# controller.net
KiCad netlist of a schematic drawn in EAGLE
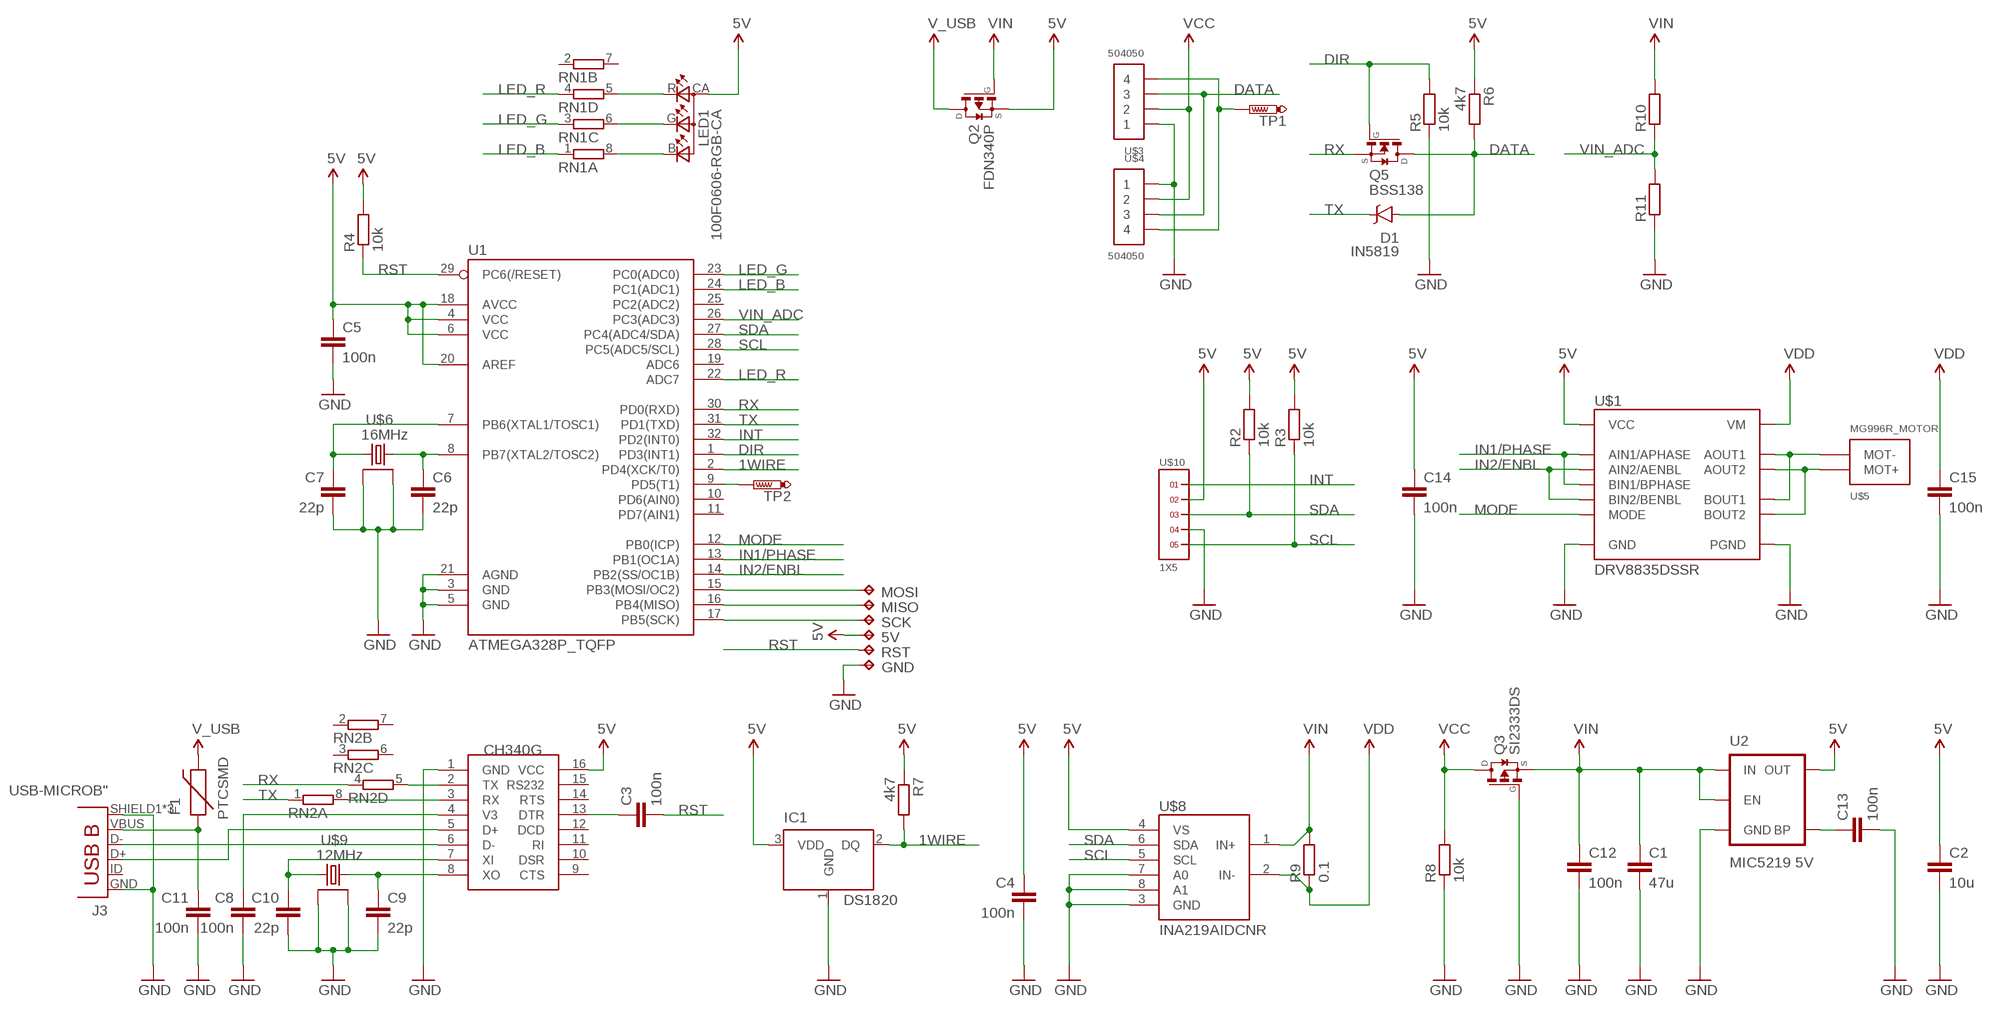
[diagram p0: schematic, sheet 1]

(export (version "E")
  (design (tool "Eeschema 10.0.6"))
  (components
    (comp (ref "5V")
      (value "TPTP07SQ")
      (footprint "eagle-import:TP07SQ")
      (libsource (lib "eagle-import") (part "TPTP07SQ"))
    )
    (comp (ref "C1")
      (value "47u")
      (footprint "eagle-import:C1206")
      (libsource (lib "eagle-import") (part "C-EUC1206"))
    )
    (comp (ref "C2")
      (value "10u")
      (footprint "eagle-import:C0603K")
      (libsource (lib "eagle-import") (part "C-EUC0603K"))
    )
    (comp (ref "C3")
      (value "100n")
      (footprint "eagle-import:C0402K")
      (libsource (lib "eagle-import") (part "C-EUC0402K"))
    )
    (comp (ref "C4")
      (value "100n")
      (footprint "eagle-import:C0402K")
      (libsource (lib "eagle-import") (part "C-EUC0402K"))
    )
    (comp (ref "C5")
      (value "100n")
      (footprint "eagle-import:C0402K")
      (libsource (lib "eagle-import") (part "C-EUC0402K"))
    )
    (comp (ref "C6")
      (value "22p")
      (footprint "eagle-import:C0402K")
      (libsource (lib "eagle-import") (part "C-EUC0402K"))
    )
    (comp (ref "C7")
      (value "22p")
      (footprint "eagle-import:C0402K")
      (libsource (lib "eagle-import") (part "C-EUC0402K"))
    )
    (comp (ref "C8")
      (value "100n")
      (footprint "eagle-import:C0402K")
      (libsource (lib "eagle-import") (part "C-EUC0402K"))
    )
    (comp (ref "C9")
      (value "22p")
      (footprint "eagle-import:C0402K")
      (libsource (lib "eagle-import") (part "C-EUC0402K"))
    )
    (comp (ref "C10")
      (value "22p")
      (footprint "eagle-import:C0402K")
      (libsource (lib "eagle-import") (part "C-EUC0402K"))
    )
    (comp (ref "C11")
      (value "100n")
      (footprint "eagle-import:C0402K")
      (libsource (lib "eagle-import") (part "C-EUC0402K"))
    )
    (comp (ref "C12")
      (value "100n")
      (footprint "eagle-import:C0402K")
      (libsource (lib "eagle-import") (part "C-EUC0402K"))
    )
    (comp (ref "C13")
      (value "100n")
      (footprint "eagle-import:C0402K")
      (libsource (lib "eagle-import") (part "C-EUC0402K"))
    )
    (comp (ref "C14")
      (value "100n")
      (footprint "eagle-import:C0402K")
      (libsource (lib "eagle-import") (part "C-EUC0402K"))
    )
    (comp (ref "C15")
      (value "100n")
      (footprint "eagle-import:C0402K")
      (libsource (lib "eagle-import") (part "C-EUC0402K"))
    )
    (comp (ref "D1")
      (value "IN5819")
      (footprint "eagle-import:SMA-DIODE")
      (libsource (lib "eagle-import") (part "MBRA140"))
    )
    (comp (ref "F1")
      (value "PTCSMD")
      (footprint "eagle-import:PTC-1206")
      (libsource (lib "eagle-import") (part "PTCSMD"))
    )
    (comp (ref "GND")
      (value "TPTP07SQ")
      (footprint "eagle-import:TP07SQ")
      (libsource (lib "eagle-import") (part "TPTP07SQ"))
    )
    (comp (ref "IC1")
      (value "DS1820")
      (footprint "eagle-import:TO-92")
      (libsource (lib "eagle-import") (part "DS1820"))
    )
    (comp (ref "J3")
      (value "USB-MICROB\"")
      (footprint "eagle-import:USB-B-MICRO-SMD_V03")
      (libsource (lib "eagle-import") (part "USB-MICROB{dblquote}"))
    )
    (comp (ref "LED1")
      (value "100F0606-RGB-CA")
      (footprint "eagle-import:1616")
      (libsource (lib "eagle-import") (part "100F0606-RGB-CA"))
    )
    (comp (ref "MISO")
      (value "TPTP07SQ")
      (footprint "eagle-import:TP07SQ")
      (libsource (lib "eagle-import") (part "TPTP07SQ"))
    )
    (comp (ref "MOSI")
      (value "TPTP07SQ")
      (footprint "eagle-import:TP07SQ")
      (libsource (lib "eagle-import") (part "TPTP07SQ"))
    )
    (comp (ref "Q2")
      (value "FDN340P")
      (footprint "eagle-import:SSOT-3")
      (libsource (lib "eagle-import") (part "FDN340P"))
    )
    (comp (ref "Q3")
      (value "SI2333DS")
      (footprint "eagle-import:SOT23")
      (libsource (lib "eagle-import") (part "SI2333DS"))
    )
    (comp (ref "Q5")
      (value "BSS138")
      (footprint "eagle-import:SOT23")
      (libsource (lib "eagle-import") (part "BSS138"))
    )
    (comp (ref "R2")
      (value "10k")
      (footprint "eagle-import:R0402")
      (libsource (lib "eagle-import") (part "R-EU_R0402"))
    )
    (comp (ref "R3")
      (value "10k")
      (footprint "eagle-import:R0402")
      (libsource (lib "eagle-import") (part "R-EU_R0402"))
    )
    (comp (ref "R4")
      (value "10k")
      (footprint "eagle-import:R0402")
      (libsource (lib "eagle-import") (part "R-EU_R0402"))
    )
    (comp (ref "R5")
      (value "10k")
      (footprint "eagle-import:R0402")
      (libsource (lib "eagle-import") (part "R-EU_R0402"))
    )
    (comp (ref "R6")
      (value "4k7")
      (footprint "eagle-import:R0402")
      (libsource (lib "eagle-import") (part "R-EU_R0402"))
    )
    (comp (ref "R7")
      (value "4k7")
      (footprint "eagle-import:R0402")
      (libsource (lib "eagle-import") (part "R-EU_R0402"))
    )
    (comp (ref "R8")
      (value "10k")
      (footprint "eagle-import:R0402")
      (libsource (lib "eagle-import") (part "R-EU_R0402"))
    )
    (comp (ref "R9")
      (value "0.1")
      (footprint "eagle-import:R2512")
      (libsource (lib "eagle-import") (part "R-EU_R2512"))
    )
    (comp (ref "R10")
      (value "R-EU_R0402")
      (footprint "eagle-import:R0402")
      (libsource (lib "eagle-import") (part "R-EU_R0402"))
    )
    (comp (ref "R11")
      (value "R-EU_R0402")
      (footprint "eagle-import:R0402")
      (libsource (lib "eagle-import") (part "R-EU_R0402"))
    )
    (comp (ref "RN1")
      (value "4R-NYC124")
      (footprint "eagle-import:YC124")
      (libsource (lib "eagle-import") (part "4R-NYC124"))
    )
    (comp (ref "RN2")
      (value "4R-NYC124")
      (footprint "eagle-import:YC124")
      (libsource (lib "eagle-import") (part "4R-NYC124"))
    )
    (comp (ref "RST")
      (value "TPTP07SQ")
      (footprint "eagle-import:TP07SQ")
      (libsource (lib "eagle-import") (part "TPTP07SQ"))
    )
    (comp (ref "SCK")
      (value "TPTP07SQ")
      (footprint "eagle-import:TP07SQ")
      (libsource (lib "eagle-import") (part "TPTP07SQ"))
    )
    (comp (ref "TP1")
      (value "PTR1TP12R")
      (footprint "eagle-import:TP12R")
      (libsource (lib "eagle-import") (part "PTR1TP12R"))
    )
    (comp (ref "TP2")
      (value "PTR1TP12R")
      (footprint "eagle-import:TP12R")
      (libsource (lib "eagle-import") (part "PTR1TP12R"))
    )
    (comp (ref "U$1")
      (value "DRV8835DSSR")
      (footprint "eagle-import:WSON-12")
      (libsource (lib "eagle-import") (part "DRV8835DSSR"))
    )
    (comp (ref "U$2")
      (value "CH340G")
      (footprint "eagle-import:SOIC16")
      (libsource (lib "eagle-import") (part "CH340G"))
    )
    (comp (ref "U$3")
      (value "504050")
      (footprint "eagle-import:504050")
      (libsource (lib "eagle-import") (part "504050"))
    )
    (comp (ref "U$4")
      (value "504050")
      (footprint "eagle-import:504050")
      (libsource (lib "eagle-import") (part "504050"))
    )
    (comp (ref "U$5")
      (value "MG996R_MOTOR")
      (footprint "eagle-import:MOTOR")
      (libsource (lib "eagle-import") (part "MG996R_MOTOR"))
    )
    (comp (ref "U$6")
      (value "16MHz")
      (footprint "eagle-import:OSC3225")
      (libsource (lib "eagle-import") (part "GSX-331"))
    )
    (comp (ref "U$8")
      (value "INA219AIDCNR")
      (footprint "eagle-import:SOT23-8L")
      (libsource (lib "eagle-import") (part "INA219AIDCNR"))
    )
    (comp (ref "U$9")
      (value "12MHz")
      (footprint "eagle-import:OSC3225")
      (libsource (lib "eagle-import") (part "GSX-331"))
    )
    (comp (ref "U$10")
      (value "1X5")
      (footprint "eagle-import:1X5")
      (libsource (lib "eagle-import") (part "1X5"))
    )
    (comp (ref "U1")
      (value "ATMEGA328P_TQFP")
      (footprint "eagle-import:TQFP32-08")
      (libsource (lib "eagle-import") (part "ATMEGA328P_TQFP"))
    )
    (comp (ref "U2")
      (value "MIC5219 5V")
      (footprint "eagle-import:SOT23-5")
      (libsource (lib "eagle-import") (part "V_REG_MIC52195V"))
    )
  )
  (nets
    (net (code "1") (name "/1WIRE") (class "Default")
      (node (ref "IC1") (pin "2") (pinfunction "DQ_2") (pintype "output"))
      (node (ref "R7") (pin "2") (pinfunction "2_2") (pintype "passive"))
      (node (ref "U1") (pin "2") (pinfunction "PD4(XCK/T0)_2") (pintype "bidirectional"))
    )
    (net (code "2") (name "/DATA") (class "Default")
      (node (ref "D1") (pin "A") (pinfunction "A_A") (pintype "passive"))
      (node (ref "Q5") (pin "3") (pinfunction "D_3") (pintype "passive"))
      (node (ref "R6") (pin "2") (pinfunction "2_2") (pintype "passive"))
      (node (ref "U$3") (pin "P$3") (pinfunction "3_P$3") (pintype "bidirectional"))
      (node (ref "U$4") (pin "P$3") (pinfunction "3_P$3") (pintype "bidirectional"))
    )
    (net (code "3") (name "/DIR") (class "Default")
      (node (ref "Q5") (pin "1") (pinfunction "G_1") (pintype "passive"))
      (node (ref "R5") (pin "2") (pinfunction "2_2") (pintype "passive"))
      (node (ref "U1") (pin "1") (pinfunction "PD3(INT1)_1") (pintype "bidirectional"))
    )
    (net (code "4") (name "/IN1{slash}PHASE") (class "Default")
      (node (ref "U$1") (pin "P$10") (pinfunction "AIN1/APHASE_P$10") (pintype "bidirectional"))
      (node (ref "U$1") (pin "P$8") (pinfunction "BIN1/BPHASE_P$8") (pintype "bidirectional"))
      (node (ref "U1") (pin "13") (pinfunction "PB1(OC1A)_13") (pintype "bidirectional"))
    )
    (net (code "5") (name "/IN2{slash}ENBL") (class "Default")
      (node (ref "U$1") (pin "P$7") (pinfunction "BIN2/BENBL_P$7") (pintype "bidirectional"))
      (node (ref "U$1") (pin "P$9") (pinfunction "AIN2/AENBL_P$9") (pintype "bidirectional"))
      (node (ref "U1") (pin "14") (pinfunction "PB2(SS/OC1B)_14") (pintype "bidirectional"))
    )
    (net (code "6") (name "/INT") (class "Default")
      (node (ref "U$10") (pin "1") (pinfunction "1_1") (pintype "bidirectional"))
      (node (ref "U1") (pin "32") (pinfunction "PD2(INT0)_32") (pintype "bidirectional"))
    )
    (net (code "7") (name "/LED_B") (class "Default")
      (node (ref "RN1") (pin "1") (pinfunction "1_1") (pintype "passive"))
      (node (ref "U1") (pin "24") (pinfunction "PC1(ADC1)_24") (pintype "bidirectional"))
    )
    (net (code "8") (name "/LED_G") (class "Default")
      (node (ref "RN1") (pin "3") (pinfunction "1_3") (pintype "passive"))
      (node (ref "U1") (pin "23") (pinfunction "PC0(ADC0)_23") (pintype "bidirectional"))
    )
    (net (code "9") (name "/LED_R") (class "Default")
      (node (ref "RN1") (pin "4") (pinfunction "1_4") (pintype "passive"))
      (node (ref "U1") (pin "22") (pinfunction "ADC7_22") (pintype "bidirectional"))
    )
    (net (code "10") (name "/MODE") (class "Default")
      (node (ref "U$1") (pin "P$11") (pinfunction "MODE_P$11") (pintype "bidirectional"))
      (node (ref "U1") (pin "12") (pinfunction "PB0(ICP)_12") (pintype "bidirectional"))
    )
    (net (code "11") (name "/RST") (class "Default")
      (node (ref "C3") (pin "2") (pinfunction "2_2") (pintype "passive"))
      (node (ref "R4") (pin "1") (pinfunction "1_1") (pintype "passive"))
      (node (ref "RST") (pin "TP") (pinfunction "TP_TP") (pintype "input"))
      (node (ref "U1") (pin "29") (pinfunction "PC6(/RESET)_29") (pintype "bidirectional"))
    )
    (net (code "12") (name "/RX") (class "Default")
      (node (ref "Q5") (pin "2") (pinfunction "S_2") (pintype "passive"))
      (node (ref "RN2") (pin "4") (pinfunction "1_4") (pintype "passive"))
      (node (ref "U1") (pin "30") (pinfunction "PD0(RXD)_30") (pintype "bidirectional"))
    )
    (net (code "13") (name "/SCL") (class "Default")
      (node (ref "R3") (pin "1") (pinfunction "1_1") (pintype "passive"))
      (node (ref "U$10") (pin "5") (pinfunction "5_5") (pintype "bidirectional"))
      (node (ref "U$8") (pin "5") (pinfunction "SCL_5") (pintype "bidirectional"))
      (node (ref "U1") (pin "28") (pinfunction "PC5(ADC5/SCL)_28") (pintype "bidirectional"))
    )
    (net (code "14") (name "/SDA") (class "Default")
      (node (ref "R2") (pin "1") (pinfunction "1_1") (pintype "passive"))
      (node (ref "U$10") (pin "3") (pinfunction "3_3") (pintype "bidirectional"))
      (node (ref "U$8") (pin "6") (pinfunction "SDA_6") (pintype "bidirectional"))
      (node (ref "U1") (pin "27") (pinfunction "PC4(ADC4/SDA)_27") (pintype "bidirectional"))
    )
    (net (code "15") (name "/TX") (class "Default")
      (node (ref "D1") (pin "C") (pinfunction "C_C") (pintype "passive"))
      (node (ref "RN2") (pin "1") (pinfunction "1_1") (pintype "passive"))
      (node (ref "U1") (pin "31") (pinfunction "PD1(TXD)_31") (pintype "bidirectional"))
    )
    (net (code "16") (name "/VIN_ADC") (class "Default")
      (node (ref "R10") (pin "1") (pinfunction "1_1") (pintype "passive"))
      (node (ref "R11") (pin "2") (pinfunction "2_2") (pintype "passive"))
      (node (ref "U1") (pin "26") (pinfunction "PC3(ADC3)_26") (pintype "bidirectional"))
    )
    (net (code "17") (name "5V") (class "Default")
      (node (ref "5V") (pin "TP") (pinfunction "TP_TP") (pintype "input"))
      (node (ref "C14") (pin "1") (pinfunction "1_1") (pintype "passive"))
      (node (ref "C2") (pin "1") (pinfunction "1_1") (pintype "passive"))
      (node (ref "C4") (pin "1") (pinfunction "1_1") (pintype "passive"))
      (node (ref "C5") (pin "1") (pinfunction "1_1") (pintype "passive"))
      (node (ref "IC1") (pin "3") (pinfunction "VDD_3") (pintype "input"))
      (node (ref "LED1") (pin "CA") (pinfunction "CA_CA") (pintype "passive"))
      (node (ref "Q2") (pin "2") (pinfunction "S_2") (pintype "passive"))
      (node (ref "R2") (pin "2") (pinfunction "2_2") (pintype "passive"))
      (node (ref "R3") (pin "2") (pinfunction "2_2") (pintype "passive"))
      (node (ref "R4") (pin "2") (pinfunction "2_2") (pintype "passive"))
      (node (ref "R6") (pin "1") (pinfunction "1_1") (pintype "passive"))
      (node (ref "R7") (pin "1") (pinfunction "1_1") (pintype "passive"))
      (node (ref "U$1") (pin "P$12") (pinfunction "VCC_P$12") (pintype "bidirectional"))
      (node (ref "U$10") (pin "2") (pinfunction "2_2") (pintype "bidirectional"))
      (node (ref "U$2") (pin "16") (pinfunction "VCC_16") (pintype "bidirectional"))
      (node (ref "U$8") (pin "4") (pinfunction "VS_4") (pintype "power_in"))
      (node (ref "U1") (pin "18") (pinfunction "AVCC_18") (pintype "bidirectional"))
      (node (ref "U1") (pin "20") (pinfunction "AREF_20") (pintype "bidirectional"))
      (node (ref "U1") (pin "4") (pinfunction "VCC_4") (pintype "bidirectional"))
      (node (ref "U1") (pin "6") (pinfunction "VCC_6") (pintype "bidirectional"))
      (node (ref "U2") (pin "5") (pinfunction "OUT_5") (pintype "passive"))
    )
    (net (code "18") (name "GND") (class "Default")
      (node (ref "C1") (pin "2") (pinfunction "2_2") (pintype "passive"))
      (node (ref "C10") (pin "2") (pinfunction "2_2") (pintype "passive"))
      (node (ref "C11") (pin "2") (pinfunction "2_2") (pintype "passive"))
      (node (ref "C12") (pin "2") (pinfunction "2_2") (pintype "passive"))
      (node (ref "C13") (pin "2") (pinfunction "2_2") (pintype "passive"))
      (node (ref "C14") (pin "2") (pinfunction "2_2") (pintype "passive"))
      (node (ref "C15") (pin "2") (pinfunction "2_2") (pintype "passive"))
      (node (ref "C2") (pin "2") (pinfunction "2_2") (pintype "passive"))
      (node (ref "C4") (pin "2") (pinfunction "2_2") (pintype "passive"))
      (node (ref "C5") (pin "2") (pinfunction "2_2") (pintype "passive"))
      (node (ref "C6") (pin "2") (pinfunction "2_2") (pintype "passive"))
      (node (ref "C7") (pin "2") (pinfunction "2_2") (pintype "passive"))
      (node (ref "C8") (pin "2") (pinfunction "2_2") (pintype "passive"))
      (node (ref "C9") (pin "2") (pinfunction "2_2") (pintype "passive"))
      (node (ref "GND") (pin "TP") (pinfunction "TP_TP") (pintype "input"))
      (node (ref "IC1") (pin "1") (pinfunction "GND_1") (pintype "power_in"))
      (node (ref "J3") (pin "GND") (pinfunction "GND_GND") (pintype "bidirectional"))
      (node (ref "J3") (pin "SHIELD1") (pinfunction "SHIELD_SHIELD1") (pintype "bidirectional"))
      (node (ref "J3") (pin "SHIELD2") (pinfunction "SHIELD_SHIELD2") (pintype "bidirectional"))
      (node (ref "J3") (pin "SHIELD3") (pinfunction "SHIELD_SHIELD3") (pintype "bidirectional"))
      (node (ref "Q3") (pin "1") (pinfunction "G_1") (pintype "passive"))
      (node (ref "R11") (pin "1") (pinfunction "1_1") (pintype "passive"))
      (node (ref "R5") (pin "1") (pinfunction "1_1") (pintype "passive"))
      (node (ref "R8") (pin "1") (pinfunction "1_1") (pintype "passive"))
      (node (ref "U$1") (pin "P$13") (pinfunction "PGND_P$13") (pintype "bidirectional"))
      (node (ref "U$1") (pin "P$14") (pinfunction "PGND_P$14") (pintype "bidirectional"))
      (node (ref "U$1") (pin "P$15") (pinfunction "PGND_P$15") (pintype "bidirectional"))
      (node (ref "U$1") (pin "P$16") (pinfunction "PGND_P$16") (pintype "bidirectional"))
      (node (ref "U$1") (pin "P$6") (pinfunction "GND_P$6") (pintype "bidirectional"))
      (node (ref "U$10") (pin "4") (pinfunction "4_4") (pintype "bidirectional"))
      (node (ref "U$2") (pin "1") (pinfunction "GND_1") (pintype "bidirectional"))
      (node (ref "U$3") (pin "P$1") (pinfunction "1_P$1") (pintype "bidirectional"))
      (node (ref "U$4") (pin "P$1") (pinfunction "1_P$1") (pintype "bidirectional"))
      (node (ref "U$6") (pin "P$2") (pinfunction "2_P$2") (pintype "passive"))
      (node (ref "U$6") (pin "P$4") (pinfunction "4_P$4") (pintype "passive"))
      (node (ref "U$8") (pin "3") (pinfunction "GND_3") (pintype "power_in"))
      (node (ref "U$8") (pin "7") (pinfunction "A0_7") (pintype "input"))
      (node (ref "U$8") (pin "8") (pinfunction "A1_8") (pintype "input"))
      (node (ref "U$9") (pin "P$2") (pinfunction "2_P$2") (pintype "passive"))
      (node (ref "U$9") (pin "P$4") (pinfunction "4_P$4") (pintype "passive"))
      (node (ref "U1") (pin "21") (pinfunction "AGND_21") (pintype "bidirectional"))
      (node (ref "U1") (pin "3") (pinfunction "GND_3") (pintype "bidirectional"))
      (node (ref "U1") (pin "5") (pinfunction "GND_5") (pintype "bidirectional"))
      (node (ref "U2") (pin "2") (pinfunction "GND_2") (pintype "input"))
    )
    (net (code "19") (name "Net-(C11-Pad1)") (class "Default")
      (node (ref "C11") (pin "1") (pinfunction "1_1") (pintype "passive"))
      (node (ref "F1") (pin "1") (pinfunction "1_1") (pintype "bidirectional"))
      (node (ref "J3") (pin "VBUS") (pinfunction "VBUS_VBUS") (pintype "bidirectional"))
    )
    (net (code "20") (name "Net-(RN1A-2)") (class "Default")
      (node (ref "LED1") (pin "B") (pinfunction "B_B") (pintype "passive"))
      (node (ref "RN1") (pin "8") (pinfunction "2_8") (pintype "passive"))
    )
    (net (code "21") (name "Net-(RN1C-2)") (class "Default")
      (node (ref "LED1") (pin "G") (pinfunction "G_G") (pintype "passive"))
      (node (ref "RN1") (pin "6") (pinfunction "2_6") (pintype "passive"))
    )
    (net (code "22") (name "Net-(RN1D-2)") (class "Default")
      (node (ref "LED1") (pin "R") (pinfunction "R_R") (pintype "passive"))
      (node (ref "RN1") (pin "5") (pinfunction "2_5") (pintype "passive"))
    )
    (net (code "23") (name "Net-(RN2A-2)") (class "Default")
      (node (ref "RN2") (pin "8") (pinfunction "2_8") (pintype "passive"))
      (node (ref "U$2") (pin "3") (pinfunction "RX_3") (pintype "bidirectional"))
    )
    (net (code "24") (name "Net-(RN2D-2)") (class "Default")
      (node (ref "RN2") (pin "5") (pinfunction "2_5") (pintype "passive"))
      (node (ref "U$2") (pin "2") (pinfunction "TX_2") (pintype "bidirectional"))
    )
    (net (code "25") (name "Net-(U$1-AOUT1)") (class "Default")
      (node (ref "U$1") (pin "P$2") (pinfunction "AOUT1_P$2") (pintype "bidirectional"))
      (node (ref "U$1") (pin "P$4") (pinfunction "BOUT1_P$4") (pintype "bidirectional"))
      (node (ref "U$5") (pin "P$3") (pinfunction "MOT-_P$3") (pintype "bidirectional"))
      (node (ref "U$5") (pin "P$4") (pinfunction "MOT-_P$4") (pintype "bidirectional"))
    )
    (net (code "26") (name "Net-(U$1-AOUT2)") (class "Default")
      (node (ref "U$1") (pin "P$3") (pinfunction "AOUT2_P$3") (pintype "bidirectional"))
      (node (ref "U$1") (pin "P$5") (pinfunction "BOUT2_P$5") (pintype "bidirectional"))
      (node (ref "U$5") (pin "P$1") (pinfunction "MOT+_P$1") (pintype "bidirectional"))
      (node (ref "U$5") (pin "P$2") (pinfunction "MOT+_P$2") (pintype "bidirectional"))
    )
    (net (code "27") (name "Net-(U$2-D+)") (class "Default")
      (node (ref "J3") (pin "D+") (pinfunction "D+_D+") (pintype "bidirectional"))
      (node (ref "U$2") (pin "5") (pinfunction "D+_5") (pintype "bidirectional"))
    )
    (net (code "28") (name "Net-(U$2-D-)") (class "Default")
      (node (ref "J3") (pin "D-") (pinfunction "D-_D-") (pintype "bidirectional"))
      (node (ref "U$2") (pin "6") (pinfunction "D-_6") (pintype "bidirectional"))
    )
    (net (code "29") (name "Net-(U$2-DTR)") (class "Default")
      (node (ref "C3") (pin "1") (pinfunction "1_1") (pintype "passive"))
      (node (ref "U$2") (pin "13") (pinfunction "DTR_13") (pintype "bidirectional"))
    )
    (net (code "30") (name "Net-(U$2-V3)") (class "Default")
      (node (ref "C8") (pin "1") (pinfunction "1_1") (pintype "passive"))
      (node (ref "U$2") (pin "4") (pinfunction "V3_4") (pintype "bidirectional"))
    )
    (net (code "31") (name "Net-(U$2-XI)") (class "Default")
      (node (ref "C10") (pin "1") (pinfunction "1_1") (pintype "passive"))
      (node (ref "U$2") (pin "7") (pinfunction "XI_7") (pintype "bidirectional"))
      (node (ref "U$9") (pin "P$3") (pinfunction "3_P$3") (pintype "passive"))
    )
    (net (code "32") (name "Net-(U$2-XO)") (class "Default")
      (node (ref "C9") (pin "1") (pinfunction "1_1") (pintype "passive"))
      (node (ref "U$2") (pin "8") (pinfunction "XO_8") (pintype "bidirectional"))
      (node (ref "U$9") (pin "P$1") (pinfunction "1_P$1") (pintype "passive"))
    )
    (net (code "33") (name "Net-(U$3-4)") (class "Default")
      (node (ref "TP1") (pin "TP") (pinfunction "TP_TP") (pintype "input"))
      (node (ref "U$3") (pin "P$4") (pinfunction "4_P$4") (pintype "bidirectional"))
      (node (ref "U$4") (pin "P$4") (pinfunction "4_P$4") (pintype "bidirectional"))
    )
    (net (code "34") (name "Net-(U$6-1)") (class "Default")
      (node (ref "C6") (pin "1") (pinfunction "1_1") (pintype "passive"))
      (node (ref "U$6") (pin "P$1") (pinfunction "1_P$1") (pintype "passive"))
      (node (ref "U1") (pin "8") (pinfunction "PB7(XTAL2/TOSC2)_8") (pintype "bidirectional"))
    )
    (net (code "35") (name "Net-(U$6-3)") (class "Default")
      (node (ref "C7") (pin "1") (pinfunction "1_1") (pintype "passive"))
      (node (ref "U$6") (pin "P$3") (pinfunction "3_P$3") (pintype "passive"))
      (node (ref "U1") (pin "7") (pinfunction "PB6(XTAL1/TOSC1)_7") (pintype "bidirectional"))
    )
    (net (code "36") (name "Net-(U1-PB3(MOSI{slash}OC2))") (class "Default")
      (node (ref "MOSI") (pin "TP") (pinfunction "TP_TP") (pintype "input"))
      (node (ref "U1") (pin "15") (pinfunction "PB3(MOSI/OC2)_15") (pintype "bidirectional"))
    )
    (net (code "37") (name "Net-(U1-PB4(MISO))") (class "Default")
      (node (ref "MISO") (pin "TP") (pinfunction "TP_TP") (pintype "input"))
      (node (ref "U1") (pin "16") (pinfunction "PB4(MISO)_16") (pintype "bidirectional"))
    )
    (net (code "38") (name "Net-(U1-PB5(SCK))") (class "Default")
      (node (ref "SCK") (pin "TP") (pinfunction "TP_TP") (pintype "input"))
      (node (ref "U1") (pin "17") (pinfunction "PB5(SCK)_17") (pintype "bidirectional"))
    )
    (net (code "39") (name "Net-(U1-PD5(T1))") (class "Default")
      (node (ref "TP2") (pin "TP") (pinfunction "TP_TP") (pintype "input"))
      (node (ref "U1") (pin "9") (pinfunction "PD5(T1)_9") (pintype "bidirectional"))
    )
    (net (code "40") (name "Net-(U2-BP)") (class "Default")
      (node (ref "C13") (pin "1") (pinfunction "1_1") (pintype "passive"))
      (node (ref "U2") (pin "4") (pinfunction "BP_4") (pintype "input"))
    )
    (net (code "41") (name "VCC") (class "Default")
      (node (ref "Q3") (pin "3") (pinfunction "D_3") (pintype "passive"))
      (node (ref "R8") (pin "2") (pinfunction "2_2") (pintype "passive"))
      (node (ref "U$3") (pin "P$2") (pinfunction "2_P$2") (pintype "bidirectional"))
      (node (ref "U$4") (pin "P$2") (pinfunction "2_P$2") (pintype "bidirectional"))
    )
    (net (code "42") (name "VDD") (class "Default")
      (node (ref "C15") (pin "1") (pinfunction "1_1") (pintype "passive"))
      (node (ref "R9") (pin "1") (pinfunction "1_1") (pintype "passive"))
      (node (ref "U$1") (pin "P$1") (pinfunction "VM_P$1") (pintype "bidirectional"))
      (node (ref "U$8") (pin "2") (pinfunction "IN-_2") (pintype "input"))
    )
    (net (code "43") (name "VIN") (class "Default")
      (node (ref "C1") (pin "1") (pinfunction "1_1") (pintype "passive"))
      (node (ref "C12") (pin "1") (pinfunction "1_1") (pintype "passive"))
      (node (ref "Q2") (pin "1") (pinfunction "G_1") (pintype "passive"))
      (node (ref "Q3") (pin "2") (pinfunction "S_2") (pintype "passive"))
      (node (ref "R10") (pin "2") (pinfunction "2_2") (pintype "passive"))
      (node (ref "R9") (pin "2") (pinfunction "2_2") (pintype "passive"))
      (node (ref "U$8") (pin "1") (pinfunction "IN+_1") (pintype "input"))
      (node (ref "U2") (pin "1") (pinfunction "IN_1") (pintype "input"))
      (node (ref "U2") (pin "3") (pinfunction "EN_3") (pintype "input"))
    )
    (net (code "44") (name "V_USB") (class "Default")
      (node (ref "F1") (pin "2") (pinfunction "2_2") (pintype "bidirectional"))
      (node (ref "Q2") (pin "3") (pinfunction "D_3") (pintype "passive"))
    )
    (net (code "45") (name "unconnected-(J3-USBID-PadID)") (class "Default")
      (node (ref "J3") (pin "ID") (pinfunction "USBID_ID") (pintype "bidirectional"))
    )
    (net (code "46") (name "unconnected-(RN1B-1-Pad2)") (class "Default")
      (node (ref "RN1") (pin "2") (pinfunction "1_2") (pintype "passive"))
    )
    (net (code "47") (name "unconnected-(RN1B-2-Pad7)") (class "Default")
      (node (ref "RN1") (pin "7") (pinfunction "2_7") (pintype "passive"))
    )
    (net (code "48") (name "unconnected-(RN2B-1-Pad2)") (class "Default")
      (node (ref "RN2") (pin "2") (pinfunction "1_2") (pintype "passive"))
    )
    (net (code "49") (name "unconnected-(RN2B-2-Pad7)") (class "Default")
      (node (ref "RN2") (pin "7") (pinfunction "2_7") (pintype "passive"))
    )
    (net (code "50") (name "unconnected-(RN2C-1-Pad3)") (class "Default")
      (node (ref "RN2") (pin "3") (pinfunction "1_3") (pintype "passive"))
    )
    (net (code "51") (name "unconnected-(RN2C-2-Pad6)") (class "Default")
      (node (ref "RN2") (pin "6") (pinfunction "2_6") (pintype "passive"))
    )
    (net (code "52") (name "unconnected-(U$2-CTS-Pad9)") (class "Default")
      (node (ref "U$2") (pin "9") (pinfunction "CTS_9") (pintype "bidirectional"))
    )
    (net (code "53") (name "unconnected-(U$2-DCD-Pad12)") (class "Default")
      (node (ref "U$2") (pin "12") (pinfunction "DCD_12") (pintype "bidirectional"))
    )
    (net (code "54") (name "unconnected-(U$2-DSR-Pad10)") (class "Default")
      (node (ref "U$2") (pin "10") (pinfunction "DSR_10") (pintype "bidirectional"))
    )
    (net (code "55") (name "unconnected-(U$2-RI-Pad11)") (class "Default")
      (node (ref "U$2") (pin "11") (pinfunction "RI_11") (pintype "bidirectional"))
    )
    (net (code "56") (name "unconnected-(U$2-RS232-Pad15)") (class "Default")
      (node (ref "U$2") (pin "15") (pinfunction "RS232_15") (pintype "bidirectional"))
    )
    (net (code "57") (name "unconnected-(U$2-RTS-Pad14)") (class "Default")
      (node (ref "U$2") (pin "14") (pinfunction "RTS_14") (pintype "bidirectional"))
    )
    (net (code "58") (name "unconnected-(U1-ADC6-Pad19)") (class "Default")
      (node (ref "U1") (pin "19") (pinfunction "ADC6_19") (pintype "bidirectional"))
    )
    (net (code "59") (name "unconnected-(U1-PC2(ADC2)-Pad25)") (class "Default")
      (node (ref "U1") (pin "25") (pinfunction "PC2(ADC2)_25") (pintype "bidirectional"))
    )
    (net (code "60") (name "unconnected-(U1-PD6(AIN0)-Pad10)") (class "Default")
      (node (ref "U1") (pin "10") (pinfunction "PD6(AIN0)_10") (pintype "bidirectional"))
    )
    (net (code "61") (name "unconnected-(U1-PD7(AIN1)-Pad11)") (class "Default")
      (node (ref "U1") (pin "11") (pinfunction "PD7(AIN1)_11") (pintype "bidirectional"))
    )
  )
)
